# Hardwiring.net
KiCad netlist of a schematic drawn in Altium Designer
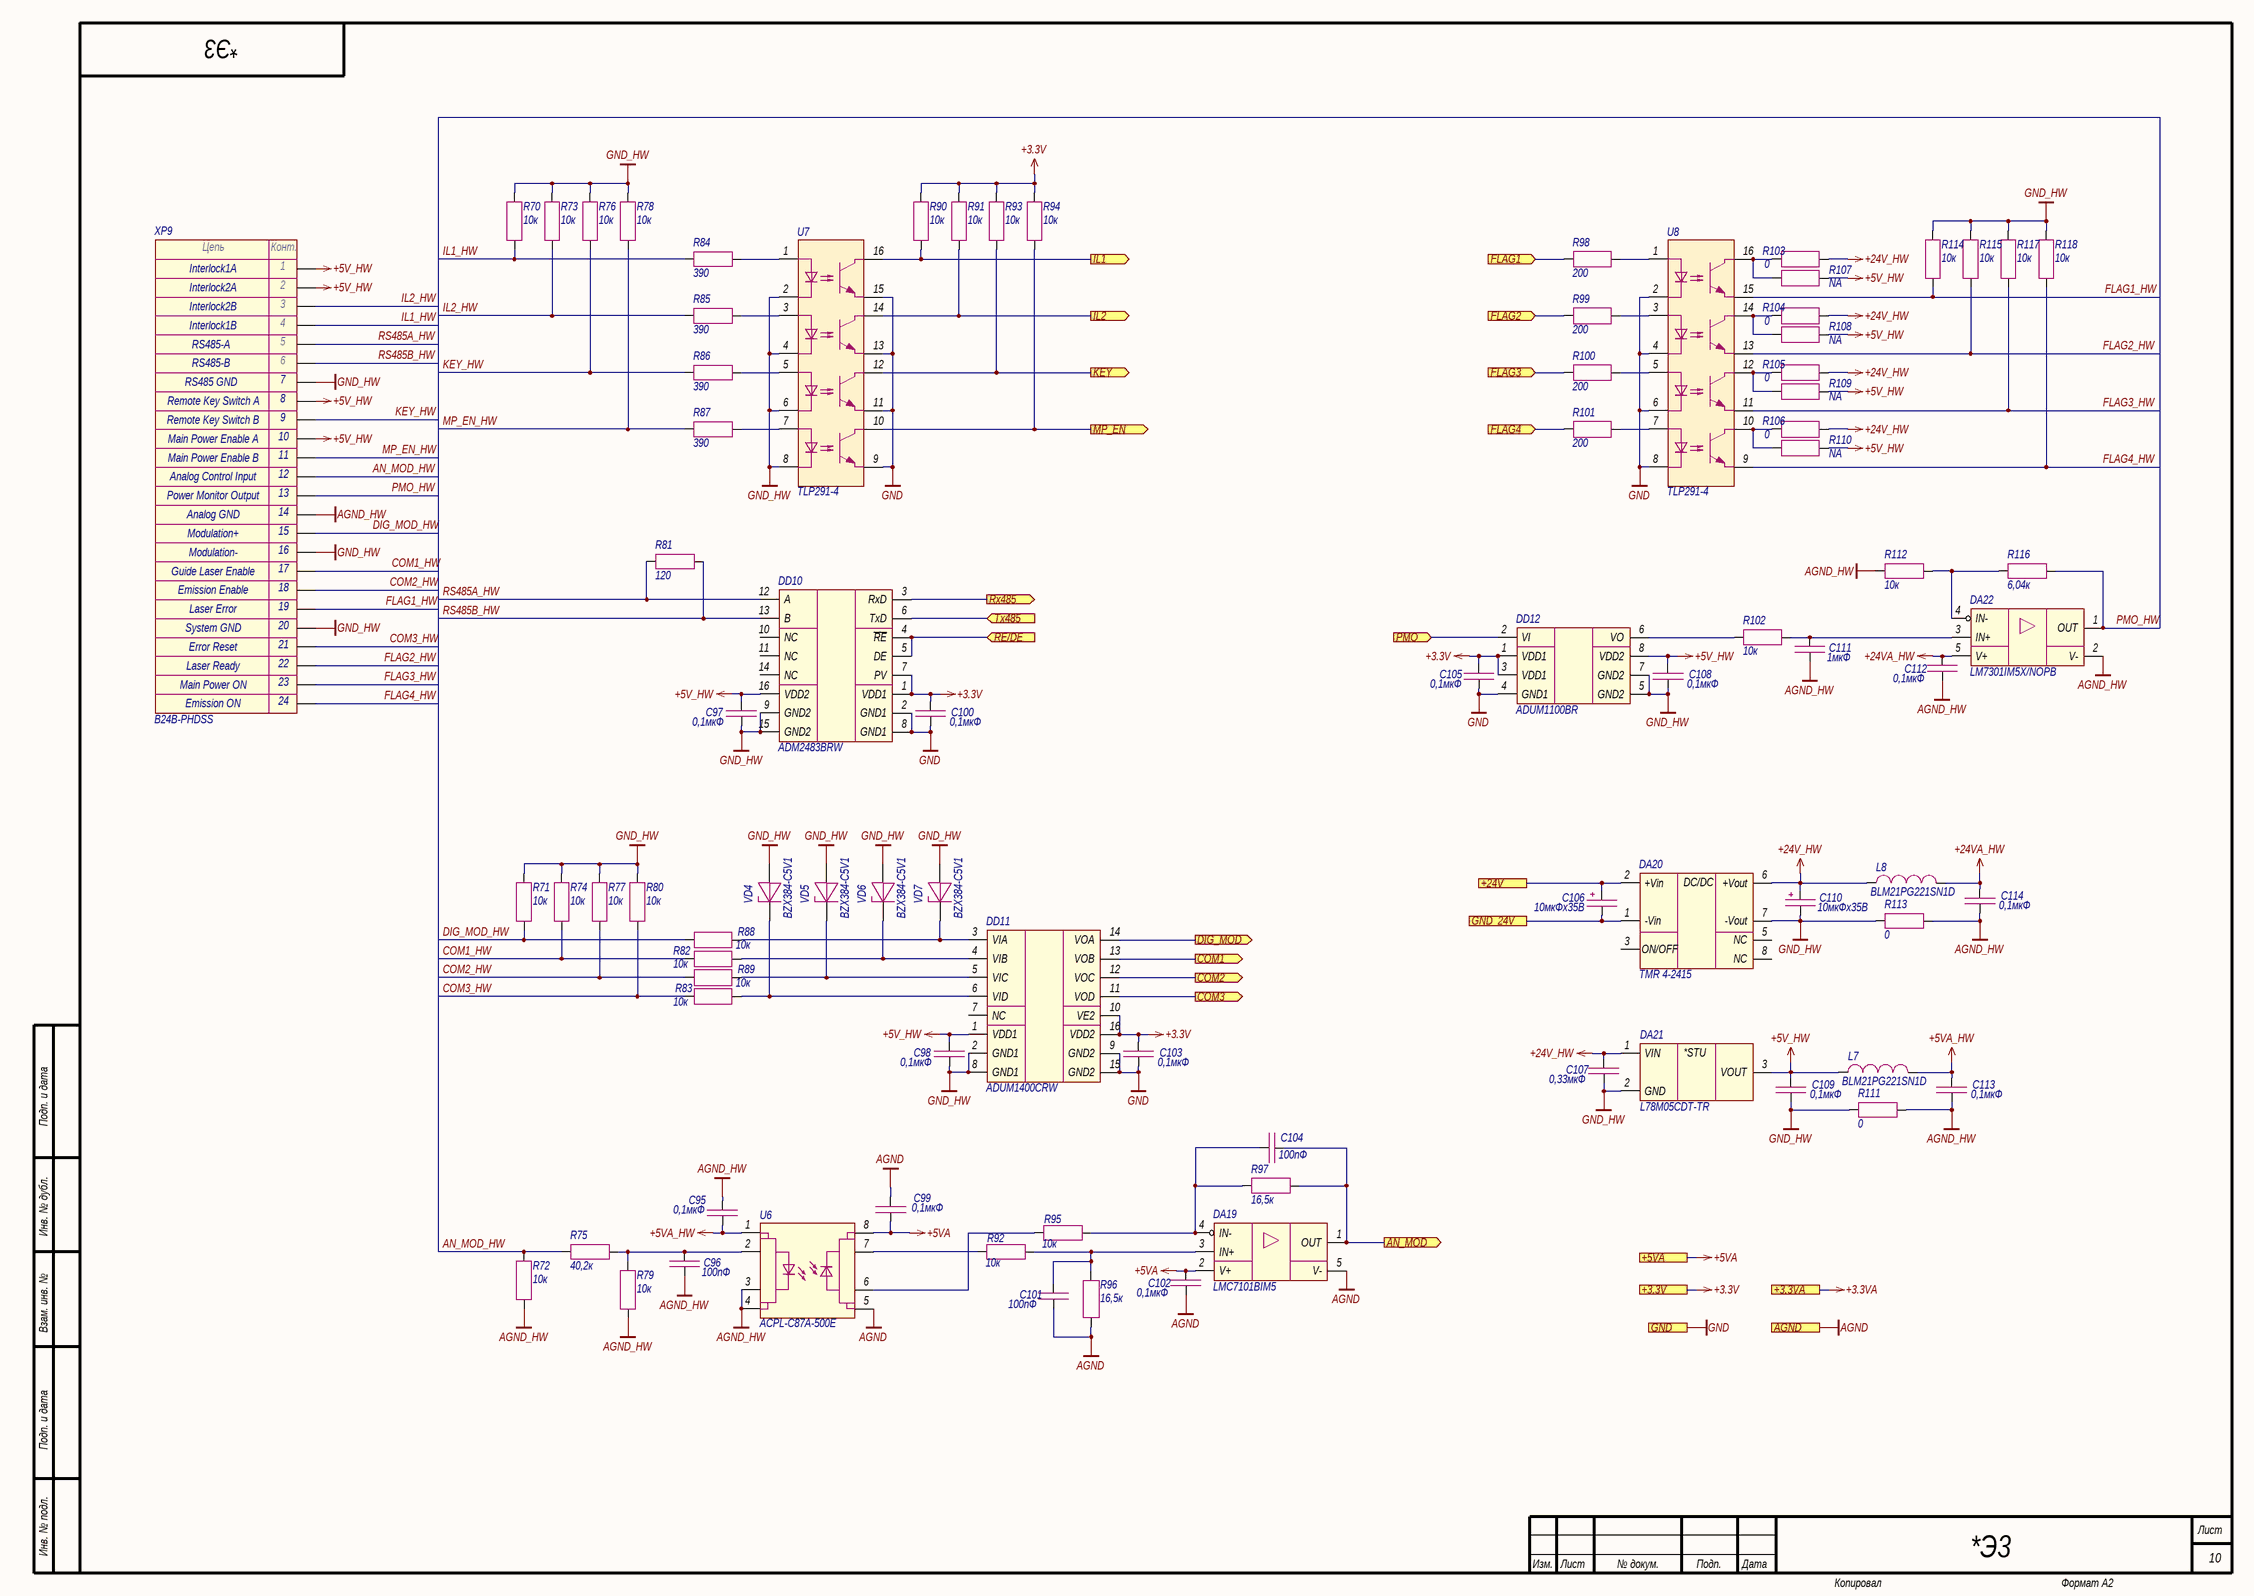
[diagram p0: Hardwiring.SchDoc]

(export (version "E")
  (design (tool "Eeschema 10.0.6"))
  (components
    (comp (ref "C95")
      (value "0,1мкФ")
      (footprint "Pcb_library:CAP_0603")
      (fields (field (name "MANUFACTURER") "Murata"))
      (libsource (lib "Schem_library") (part "Capacitor"))
    )
    (comp (ref "C96")
      (value "100пФ")
      (footprint "Pcb_library:CAP_0603")
      (fields (field (name "MANUFACTURER") "Murata"))
      (libsource (lib "Schem_library") (part "Capacitor"))
    )
    (comp (ref "C97")
      (value "0,1мкФ")
      (footprint "Pcb_library:CAP_0603")
      (fields (field (name "MANUFACTURER") "Murata"))
      (libsource (lib "Schem_library") (part "Capacitor"))
    )
    (comp (ref "C98")
      (value "0,1мкФ")
      (footprint "Pcb_library:CAP_0603")
      (fields (field (name "MANUFACTURER") "Murata"))
      (libsource (lib "Schem_library") (part "Capacitor"))
    )
    (comp (ref "C99")
      (value "0,1мкФ")
      (footprint "Pcb_library:CAP_0603")
      (fields (field (name "MANUFACTURER") "Murata"))
      (libsource (lib "Schem_library") (part "Capacitor"))
    )
    (comp (ref "C100")
      (value "0,1мкФ")
      (footprint "Pcb_library:CAP_0603")
      (fields (field (name "MANUFACTURER") "Murata"))
      (libsource (lib "Schem_library") (part "Capacitor"))
    )
    (comp (ref "C101")
      (value "100пФ")
      (footprint "Pcb_library:CAP_0603")
      (fields (field (name "MANUFACTURER") "Murata"))
      (libsource (lib "Schem_library") (part "Capacitor"))
    )
    (comp (ref "C102")
      (value "0,1мкФ")
      (footprint "Pcb_library:CAP_0603")
      (fields (field (name "MANUFACTURER") "Murata"))
      (libsource (lib "Schem_library") (part "Capacitor"))
    )
    (comp (ref "C103")
      (value "0,1мкФ")
      (footprint "Pcb_library:CAP_0603")
      (fields (field (name "MANUFACTURER") "Murata"))
      (libsource (lib "Schem_library") (part "Capacitor"))
    )
    (comp (ref "C104")
      (value "100пФ")
      (footprint "Pcb_library:CAP_0603")
      (fields (field (name "MANUFACTURER") "Murata"))
      (libsource (lib "Schem_library") (part "Capacitor"))
    )
    (comp (ref "C105")
      (value "0,1мкФ")
      (footprint "Pcb_library:CAP_0603")
      (fields (field (name "MANUFACTURER") "Murata"))
      (libsource (lib "Schem_library") (part "Capacitor"))
    )
    (comp (ref "C106")
      (value "10мкФх35B")
      (footprint "Pcb_library:CAP_C")
      (libsource (lib "Schem_library") (part "Capacitor_Polar"))
    )
    (comp (ref "C107")
      (value "0,33мкФ")
      (footprint "Pcb_library:CAP_0805")
      (fields (field (name "MANUFACTURER") "Murata"))
      (libsource (lib "Schem_library") (part "Capacitor"))
    )
    (comp (ref "C108")
      (value "0,1мкФ")
      (footprint "Pcb_library:CAP_0603")
      (fields (field (name "MANUFACTURER") "Murata"))
      (libsource (lib "Schem_library") (part "Capacitor"))
    )
    (comp (ref "C109")
      (value "0,1мкФ")
      (footprint "Pcb_library:CAP_0603")
      (fields (field (name "MANUFACTURER") "Murata"))
      (libsource (lib "Schem_library") (part "Capacitor"))
    )
    (comp (ref "C110")
      (value "10мкФх35B")
      (footprint "Pcb_library:CAP_C")
      (libsource (lib "") (part "Capacitor_Polar_1"))
    )
    (comp (ref "C111")
      (value "1мкФ")
      (footprint "Pcb_library:CAP_0603")
      (fields (field (name "MANUFACTURER") "Murata"))
      (libsource (lib "Schem_library") (part "Capacitor"))
    )
    (comp (ref "C112")
      (value "0,1мкФ")
      (footprint "Pcb_library:CAP_0603")
      (fields (field (name "MANUFACTURER") "Murata"))
      (libsource (lib "Schem_library") (part "Capacitor"))
    )
    (comp (ref "C113")
      (value "0,1мкФ")
      (footprint "Pcb_library:CAP_0603")
      (fields (field (name "MANUFACTURER") "Murata"))
      (libsource (lib "Schem_library") (part "Capacitor"))
    )
    (comp (ref "C114")
      (value "0,1мкФ")
      (footprint "Pcb_library:CAP_0603")
      (fields (field (name "MANUFACTURER") "Murata"))
      (libsource (lib "Schem_library") (part "Capacitor"))
    )
    (comp (ref "DA19")
      (value "LMC7101BIM5")
      (footprint "Pcb_library:SOT-23-5")
      (fields (field (name "MANUFACTURER") "Texas Instruments"))
      (libsource (lib "Schem_library") (part "LMC7101"))
    )
    (comp (ref "DA20")
      (value "TMR 4-2415")
      (footprint "Pcb_library:TMR4 (SIP-8)")
      (fields (field (name "MANUFACTURER") "Traco Power"))
      (libsource (lib "Schem_library") (part "TMR4"))
    )
    (comp (ref "DA21")
      (value "L78M05CDT-TR")
      (footprint "Pcb_library:TO-252")
      (fields (field (name "MANUFACTURER") "STMicroelectronics"))
      (libsource (lib "Schem_library") (part "L78M"))
    )
    (comp (ref "DA22")
      (value "LM7301IM5X/NOPB")
      (footprint "Pcb_library:SOT-23-5")
      (fields (field (name "MANUFACTURER") "Texas Instruments"))
      (libsource (lib "Schem_library") (part "LM7301IM5"))
    )
    (comp (ref "DD10")
      (value "ADM2483BRW")
      (footprint "Pcb_library:SOIC-16W")
      (fields (field (name "MANUFACTURER") "Analog Devices"))
      (libsource (lib "Schem_library") (part "ADM2483BRW"))
    )
    (comp (ref "DD11")
      (value "ADUM1400CRW")
      (footprint "Pcb_library:SOIC-16W")
      (fields (field (name "MANUFACTURER") "Analog Devices"))
      (libsource (lib "Schem_library") (part "ADUM1400"))
    )
    (comp (ref "DD12")
      (value "ADUM1100BR")
      (footprint "Pcb_library:SOIC-8")
      (fields (field (name "MANUFACTURER") "Analog Devices"))
      (libsource (lib "Schem_library") (part "ADUM1100"))
    )
    (comp (ref "L7")
      (value "BLM21PG221SN1D")
      (footprint "Pcb_library:IND_0805")
      (fields (field (name "MANUFACTURER") "Murata"))
      (libsource (lib "Schem_library") (part "Inductor"))
    )
    (comp (ref "L8")
      (value "BLM21PG221SN1D")
      (footprint "Pcb_library:IND_0805")
      (fields (field (name "MANUFACTURER") "Murata"))
      (libsource (lib "Schem_library") (part "Inductor"))
    )
    (comp (ref "R70")
      (value "10к")
      (footprint "Pcb_library:RES_0603")
      (fields (field (name "MANUFACTURER") "Yageo"))
      (libsource (lib "Schem_library") (part "Resistor"))
    )
    (comp (ref "R71")
      (value "10к")
      (footprint "Pcb_library:RES_0603")
      (fields (field (name "MANUFACTURER") "Yageo"))
      (libsource (lib "Schem_library") (part "Resistor"))
    )
    (comp (ref "R72")
      (value "10к")
      (footprint "Pcb_library:RES_0603")
      (fields (field (name "MANUFACTURER") "Yageo"))
      (libsource (lib "Schem_library") (part "Resistor"))
    )
    (comp (ref "R73")
      (value "10к")
      (footprint "Pcb_library:RES_0603")
      (fields (field (name "MANUFACTURER") "Yageo"))
      (libsource (lib "Schem_library") (part "Resistor"))
    )
    (comp (ref "R74")
      (value "10к")
      (footprint "Pcb_library:RES_0603")
      (fields (field (name "MANUFACTURER") "Yageo"))
      (libsource (lib "Schem_library") (part "Resistor"))
    )
    (comp (ref "R75")
      (value "40,2к")
      (footprint "Pcb_library:RES_0603")
      (fields (field (name "MANUFACTURER") "Yageo"))
      (libsource (lib "Schem_library") (part "Resistor"))
    )
    (comp (ref "R76")
      (value "10к")
      (footprint "Pcb_library:RES_0603")
      (fields (field (name "MANUFACTURER") "Yageo"))
      (libsource (lib "Schem_library") (part "Resistor"))
    )
    (comp (ref "R77")
      (value "10к")
      (footprint "Pcb_library:RES_0603")
      (fields (field (name "MANUFACTURER") "Yageo"))
      (libsource (lib "Schem_library") (part "Resistor"))
    )
    (comp (ref "R78")
      (value "10к")
      (footprint "Pcb_library:RES_0603")
      (fields (field (name "MANUFACTURER") "Yageo"))
      (libsource (lib "Schem_library") (part "Resistor"))
    )
    (comp (ref "R79")
      (value "10к")
      (footprint "Pcb_library:RES_0603")
      (fields (field (name "MANUFACTURER") "Yageo"))
      (libsource (lib "Schem_library") (part "Resistor"))
    )
    (comp (ref "R80")
      (value "10к")
      (footprint "Pcb_library:RES_0603")
      (fields (field (name "MANUFACTURER") "Yageo"))
      (libsource (lib "Schem_library") (part "Resistor"))
    )
    (comp (ref "R81")
      (value "120")
      (footprint "Pcb_library:RES_0805")
      (fields (field (name "MANUFACTURER") "Yageo"))
      (libsource (lib "Schem_library") (part "Resistor"))
    )
    (comp (ref "R82")
      (value "10к")
      (footprint "Pcb_library:RES_0603")
      (fields (field (name "MANUFACTURER") "Yageo"))
      (libsource (lib "Schem_library") (part "Resistor"))
    )
    (comp (ref "R83")
      (value "10к")
      (footprint "Pcb_library:RES_0603")
      (fields (field (name "MANUFACTURER") "Yageo"))
      (libsource (lib "Schem_library") (part "Resistor"))
    )
    (comp (ref "R84")
      (value "390")
      (footprint "Pcb_library:RES_0603")
      (fields (field (name "MANUFACTURER") "Yageo"))
      (libsource (lib "Schem_library") (part "Resistor"))
    )
    (comp (ref "R85")
      (value "390")
      (footprint "Pcb_library:RES_0603")
      (fields (field (name "MANUFACTURER") "Yageo"))
      (libsource (lib "Schem_library") (part "Resistor"))
    )
    (comp (ref "R86")
      (value "390")
      (footprint "Pcb_library:RES_0603")
      (fields (field (name "MANUFACTURER") "Yageo"))
      (libsource (lib "Schem_library") (part "Resistor"))
    )
    (comp (ref "R87")
      (value "390")
      (footprint "Pcb_library:RES_0603")
      (fields (field (name "MANUFACTURER") "Yageo"))
      (libsource (lib "Schem_library") (part "Resistor"))
    )
    (comp (ref "R88")
      (value "10к")
      (footprint "Pcb_library:RES_0603")
      (fields (field (name "MANUFACTURER") "Yageo"))
      (libsource (lib "Schem_library") (part "Resistor"))
    )
    (comp (ref "R89")
      (value "10к")
      (footprint "Pcb_library:RES_0603")
      (fields (field (name "MANUFACTURER") "Yageo"))
      (libsource (lib "Schem_library") (part "Resistor"))
    )
    (comp (ref "R90")
      (value "10к")
      (footprint "Pcb_library:RES_0603")
      (fields (field (name "MANUFACTURER") "Yageo"))
      (libsource (lib "Schem_library") (part "Resistor"))
    )
    (comp (ref "R91")
      (value "10к")
      (footprint "Pcb_library:RES_0603")
      (fields (field (name "MANUFACTURER") "Yageo"))
      (libsource (lib "Schem_library") (part "Resistor"))
    )
    (comp (ref "R92")
      (value "10к")
      (footprint "Pcb_library:RES_0603")
      (fields (field (name "MANUFACTURER") "Yageo"))
      (libsource (lib "Schem_library") (part "Resistor"))
    )
    (comp (ref "R93")
      (value "10к")
      (footprint "Pcb_library:RES_0603")
      (fields (field (name "MANUFACTURER") "Yageo"))
      (libsource (lib "Schem_library") (part "Resistor"))
    )
    (comp (ref "R94")
      (value "10к")
      (footprint "Pcb_library:RES_0603")
      (fields (field (name "MANUFACTURER") "Yageo"))
      (libsource (lib "Schem_library") (part "Resistor"))
    )
    (comp (ref "R95")
      (value "10к")
      (footprint "Pcb_library:RES_0603")
      (fields (field (name "MANUFACTURER") "Yageo"))
      (libsource (lib "Schem_library") (part "Resistor"))
    )
    (comp (ref "R96")
      (value "16,5к")
      (footprint "Pcb_library:RES_0603")
      (fields (field (name "MANUFACTURER") "Yageo"))
      (libsource (lib "Schem_library") (part "Resistor"))
    )
    (comp (ref "R97")
      (value "16,5к")
      (footprint "Pcb_library:RES_0603")
      (fields (field (name "MANUFACTURER") "Yageo"))
      (libsource (lib "Schem_library") (part "Resistor"))
    )
    (comp (ref "R98")
      (value "200")
      (footprint "Pcb_library:RES_0603")
      (fields (field (name "MANUFACTURER") "Yageo"))
      (libsource (lib "Schem_library") (part "Resistor"))
    )
    (comp (ref "R99")
      (value "200")
      (footprint "Pcb_library:RES_0603")
      (fields (field (name "MANUFACTURER") "Yageo"))
      (libsource (lib "Schem_library") (part "Resistor"))
    )
    (comp (ref "R100")
      (value "200")
      (footprint "Pcb_library:RES_0603")
      (fields (field (name "MANUFACTURER") "Yageo"))
      (libsource (lib "Schem_library") (part "Resistor"))
    )
    (comp (ref "R101")
      (value "200")
      (footprint "Pcb_library:RES_0603")
      (fields (field (name "MANUFACTURER") "Yageo"))
      (libsource (lib "Schem_library") (part "Resistor"))
    )
    (comp (ref "R102")
      (value "10к")
      (footprint "Pcb_library:RES_0603")
      (fields (field (name "MANUFACTURER") "Yageo"))
      (libsource (lib "Schem_library") (part "Resistor"))
    )
    (comp (ref "R103")
      (value "0")
      (footprint "Pcb_library:RES_0603")
      (fields (field (name "MANUFACTURER") "Yageo"))
      (libsource (lib "Schem_library") (part "Resistor"))
    )
    (comp (ref "R104")
      (value "0")
      (footprint "Pcb_library:RES_0603")
      (fields (field (name "MANUFACTURER") "Yageo"))
      (libsource (lib "Schem_library") (part "Resistor"))
    )
    (comp (ref "R105")
      (value "0")
      (footprint "Pcb_library:RES_0603")
      (fields (field (name "MANUFACTURER") "Yageo"))
      (libsource (lib "Schem_library") (part "Resistor"))
    )
    (comp (ref "R106")
      (value "0")
      (footprint "Pcb_library:RES_0603")
      (fields (field (name "MANUFACTURER") "Yageo"))
      (libsource (lib "Schem_library") (part "Resistor"))
    )
    (comp (ref "R107")
      (value "NA")
      (footprint "Pcb_library:RES_0603")
      (libsource (lib "Schem_library") (part "Resistor"))
    )
    (comp (ref "R108")
      (value "NA")
      (footprint "Pcb_library:RES_0603")
      (libsource (lib "Schem_library") (part "Resistor"))
    )
    (comp (ref "R109")
      (value "NA")
      (footprint "Pcb_library:RES_0603")
      (libsource (lib "Schem_library") (part "Resistor"))
    )
    (comp (ref "R110")
      (value "NA")
      (footprint "Pcb_library:RES_0603")
      (libsource (lib "Schem_library") (part "Resistor"))
    )
    (comp (ref "R111")
      (value "0")
      (footprint "Pcb_library:RES_0805")
      (fields (field (name "MANUFACTURER") "Yageo"))
      (libsource (lib "Schem_library") (part "Resistor"))
    )
    (comp (ref "R112")
      (value "10к")
      (footprint "Pcb_library:RES_0603")
      (fields (field (name "MANUFACTURER") "Yageo"))
      (libsource (lib "Schem_library") (part "Resistor"))
    )
    (comp (ref "R113")
      (value "0")
      (footprint "Pcb_library:RES_0805")
      (fields (field (name "MANUFACTURER") "Yageo"))
      (libsource (lib "Schem_library") (part "Resistor"))
    )
    (comp (ref "R114")
      (value "10к")
      (footprint "Pcb_library:RES_0603")
      (fields (field (name "MANUFACTURER") "Yageo"))
      (libsource (lib "Schem_library") (part "Resistor"))
    )
    (comp (ref "R115")
      (value "10к")
      (footprint "Pcb_library:RES_0603")
      (fields (field (name "MANUFACTURER") "Yageo"))
      (libsource (lib "Schem_library") (part "Resistor"))
    )
    (comp (ref "R116")
      (value "6,04к")
      (footprint "Pcb_library:RES_0603")
      (fields (field (name "MANUFACTURER") "Yageo"))
      (libsource (lib "Schem_library") (part "Resistor"))
    )
    (comp (ref "R117")
      (value "10к")
      (footprint "Pcb_library:RES_0603")
      (fields (field (name "MANUFACTURER") "Yageo"))
      (libsource (lib "Schem_library") (part "Resistor"))
    )
    (comp (ref "R118")
      (value "10к")
      (footprint "Pcb_library:RES_0603")
      (fields (field (name "MANUFACTURER") "Yageo"))
      (libsource (lib "Schem_library") (part "Resistor"))
    )
    (comp (ref "U6")
      (value "ACPL-C87A-500E")
      (footprint "Pcb_library:SSO-8")
      (fields (field (name "MANUFACTURER") "Broadcom"))
      (libsource (lib "Schem_library") (part "ACPL-C87"))
    )
    (comp (ref "U7")
      (value "TLP291-4")
      (footprint "Pcb_library:SOP-16")
      (fields (field (name "MANUFACTURER") "Toshiba"))
      (libsource (lib "Schem_library") (part "TLP281-4"))
    )
    (comp (ref "U8")
      (value "TLP291-4")
      (footprint "Pcb_library:SOP-16")
      (fields (field (name "MANUFACTURER") "Toshiba"))
      (libsource (lib "Schem_library") (part "TLP281-4"))
    )
    (comp (ref "VD4")
      (value "BZX384-C5V1")
      (footprint "Pcb_library:SOD-323")
      (fields (field (name "MANUFACTURER") "Nexperia"))
      (libsource (lib "Schem_library") (part "Diode_Zener"))
    )
    (comp (ref "VD5")
      (value "BZX384-C5V1")
      (footprint "Pcb_library:SOD-323")
      (fields (field (name "MANUFACTURER") "Nexperia"))
      (libsource (lib "Schem_library") (part "Diode_Zener"))
    )
    (comp (ref "VD6")
      (value "BZX384-C5V1")
      (footprint "Pcb_library:SOD-323")
      (fields (field (name "MANUFACTURER") "Nexperia"))
      (libsource (lib "Schem_library") (part "Diode_Zener"))
    )
    (comp (ref "VD7")
      (value "BZX384-C5V1")
      (footprint "Pcb_library:SOD-323")
      (fields (field (name "MANUFACTURER") "Nexperia"))
      (libsource (lib "Schem_library") (part "Diode_Zener"))
    )
    (comp (ref "XP9")
      (value "B24B-PHDSS")
      (footprint "Pcb_library:B24B-PHDSS")
      (fields (field (name "MANUFACTURER") "JST"))
      (libsource (lib "Schem_library") (part "Connector-24"))
    )
  )
  (nets
    (net (code "1") (name "+3.3V") (class "Default")
      (node (ref "C100") (pin "1") (pinfunction "1_1") (pintype "passive"))
      (node (ref "C103") (pin "1") (pinfunction "1_1") (pintype "passive"))
      (node (ref "C105") (pin "1") (pinfunction "1_1") (pintype "passive"))
      (node (ref "DD10") (pin "1") (pinfunction "VDD1_1") (pintype "passive"))
      (node (ref "DD10") (pin "7") (pinfunction "PV_7") (pintype "passive"))
      (node (ref "DD11") (pin "10") (pinfunction "VE2_10") (pintype "passive"))
      (node (ref "DD11") (pin "16") (pinfunction "VDD2_16") (pintype "passive"))
      (node (ref "DD12") (pin "1") (pinfunction "VDD1_1") (pintype "passive"))
      (node (ref "DD12") (pin "3") (pinfunction "VDD1_3") (pintype "passive"))
      (node (ref "R90") (pin "1") (pinfunction "1_1") (pintype "passive"))
      (node (ref "R91") (pin "1") (pinfunction "1_1") (pintype "passive"))
      (node (ref "R93") (pin "1") (pinfunction "1_1") (pintype "passive"))
      (node (ref "R94") (pin "1") (pinfunction "1_1") (pintype "passive"))
    )
    (net (code "3") (name "+5VA") (class "Default")
      (node (ref "C102") (pin "1") (pinfunction "1_1") (pintype "passive"))
      (node (ref "C99") (pin "1") (pinfunction "1_1") (pintype "passive"))
      (node (ref "DA19") (pin "2") (pinfunction "V+_2") (pintype "passive"))
      (node (ref "U6") (pin "8") (pinfunction "VDD2_8") (pintype "passive"))
    )
    (net (code "4") (name "+5VA_HW") (class "Default")
      (node (ref "C113") (pin "1") (pinfunction "1_1") (pintype "passive"))
      (node (ref "C95") (pin "1") (pinfunction "1_1") (pintype "passive"))
      (node (ref "L7") (pin "2") (pinfunction "2_2") (pintype "passive"))
      (node (ref "U6") (pin "1") (pinfunction "VDD1_1") (pintype "passive"))
    )
    (net (code "5") (name "+5V_HW") (class "Default")
      (node (ref "C108") (pin "1") (pinfunction "1_1") (pintype "passive"))
      (node (ref "C109") (pin "1") (pinfunction "1_1") (pintype "passive"))
      (node (ref "C97") (pin "1") (pinfunction "1_1") (pintype "passive"))
      (node (ref "C98") (pin "1") (pinfunction "1_1") (pintype "passive"))
      (node (ref "DA21") (pin "3") (pinfunction "VOUT_3") (pintype "passive"))
      (node (ref "DD10") (pin "16") (pinfunction "VDD2_16") (pintype "passive"))
      (node (ref "DD11") (pin "1") (pinfunction "VDD1_1") (pintype "passive"))
      (node (ref "DD12") (pin "8") (pinfunction "VDD2_8") (pintype "passive"))
      (node (ref "L7") (pin "1") (pinfunction "1_1") (pintype "passive"))
      (node (ref "R107") (pin "2") (pinfunction "2_2") (pintype "passive"))
      (node (ref "R108") (pin "2") (pinfunction "2_2") (pintype "passive"))
      (node (ref "R109") (pin "2") (pinfunction "2_2") (pintype "passive"))
      (node (ref "R110") (pin "2") (pinfunction "2_2") (pintype "passive"))
      (node (ref "XP9") (pin "1") (pintype "passive"))
      (node (ref "XP9") (pin "10") (pintype "passive"))
      (node (ref "XP9") (pin "2") (pintype "passive"))
      (node (ref "XP9") (pin "8") (pintype "passive"))
    )
    (net (code "6") (name "+24VA_HW") (class "Default")
      (node (ref "C112") (pin "1") (pinfunction "1_1") (pintype "passive"))
      (node (ref "C114") (pin "1") (pinfunction "1_1") (pintype "passive"))
      (node (ref "DA22") (pin "5") (pinfunction "V+_5") (pintype "passive"))
      (node (ref "L8") (pin "2") (pinfunction "2_2") (pintype "passive"))
    )
    (net (code "7") (name "+24V_HW") (class "Default")
      (node (ref "C107") (pin "2") (pinfunction "2_2") (pintype "passive"))
      (node (ref "C110") (pin "1") (pinfunction "1_1") (pintype "passive"))
      (node (ref "DA20") (pin "6") (pinfunction "+Vout_6") (pintype "passive"))
      (node (ref "DA21") (pin "1") (pinfunction "VIN_1") (pintype "passive"))
      (node (ref "L8") (pin "1") (pinfunction "1_1") (pintype "passive"))
      (node (ref "R103") (pin "2") (pinfunction "2_2") (pintype "passive"))
      (node (ref "R104") (pin "2") (pinfunction "2_2") (pintype "passive"))
      (node (ref "R105") (pin "2") (pinfunction "2_2") (pintype "passive"))
      (node (ref "R106") (pin "2") (pinfunction "2_2") (pintype "passive"))
    )
    (net (code "8") (name "/+24V") (class "Default")
      (node (ref "C106") (pin "1") (pinfunction "1_1") (pintype "passive"))
      (node (ref "DA20") (pin "2") (pinfunction "+Vin_2") (pintype "passive"))
    )
    (net (code "9") (name "/AN_MOD") (class "Default")
      (node (ref "C104") (pin "2") (pinfunction "2_2") (pintype "passive"))
      (node (ref "DA19") (pin "1") (pinfunction "OUT_1") (pintype "passive"))
      (node (ref "R97") (pin "1") (pinfunction "1_1") (pintype "passive"))
    )
    (net (code "10") (name "/AN_MOD_HW") (class "Default")
      (node (ref "R72") (pin "1") (pinfunction "1_1") (pintype "passive"))
      (node (ref "R75") (pin "2") (pinfunction "2_2") (pintype "passive"))
      (node (ref "XP9") (pin "12") (pintype "passive"))
    )
    (net (code "11") (name "/COM1") (class "Default")
      (node (ref "DD11") (pin "13") (pinfunction "VOB_13") (pintype "passive"))
    )
    (net (code "12") (name "/COM1_HW") (class "Default")
      (node (ref "R74") (pin "2") (pinfunction "2_2") (pintype "passive"))
      (node (ref "R82") (pin "1") (pinfunction "1_1") (pintype "passive"))
      (node (ref "XP9") (pin "17") (pintype "passive"))
    )
    (net (code "13") (name "/COM2") (class "Default")
      (node (ref "DD11") (pin "12") (pinfunction "VOC_12") (pintype "passive"))
    )
    (net (code "14") (name "/COM2_HW") (class "Default")
      (node (ref "R77") (pin "2") (pinfunction "2_2") (pintype "passive"))
      (node (ref "R89") (pin "1") (pinfunction "1_1") (pintype "passive"))
      (node (ref "XP9") (pin "18") (pintype "passive"))
    )
    (net (code "15") (name "/COM3") (class "Default")
      (node (ref "DD11") (pin "11") (pinfunction "VOD_11") (pintype "passive"))
    )
    (net (code "16") (name "/COM3_HW") (class "Default")
      (node (ref "R80") (pin "2") (pinfunction "2_2") (pintype "passive"))
      (node (ref "R83") (pin "1") (pinfunction "1_1") (pintype "passive"))
      (node (ref "XP9") (pin "21") (pintype "passive"))
    )
    (net (code "17") (name "/DIG_MOD") (class "Default")
      (node (ref "DD11") (pin "14") (pinfunction "VOA_14") (pintype "passive"))
    )
    (net (code "18") (name "/DIG_MOD_HW") (class "Default")
      (node (ref "R71") (pin "2") (pinfunction "2_2") (pintype "passive"))
      (node (ref "R88") (pin "1") (pinfunction "1_1") (pintype "passive"))
      (node (ref "XP9") (pin "15") (pintype "passive"))
    )
    (net (code "19") (name "/FLAG1") (class "Default")
      (node (ref "R98") (pin "2") (pinfunction "2_2") (pintype "passive"))
    )
    (net (code "20") (name "/FLAG1_HW") (class "Default")
      (node (ref "R114") (pin "2") (pinfunction "2_2") (pintype "passive"))
      (node (ref "U8") (pin "15") (pintype "passive"))
      (node (ref "XP9") (pin "19") (pintype "passive"))
    )
    (net (code "21") (name "/FLAG2") (class "Default")
      (node (ref "R99") (pin "2") (pinfunction "2_2") (pintype "passive"))
    )
    (net (code "22") (name "/FLAG2_HW") (class "Default")
      (node (ref "R115") (pin "2") (pinfunction "2_2") (pintype "passive"))
      (node (ref "U8") (pin "13") (pintype "passive"))
      (node (ref "XP9") (pin "22") (pintype "passive"))
    )
    (net (code "23") (name "/FLAG3") (class "Default")
      (node (ref "R100") (pin "2") (pinfunction "2_2") (pintype "passive"))
    )
    (net (code "24") (name "/FLAG3_HW") (class "Default")
      (node (ref "R117") (pin "2") (pinfunction "2_2") (pintype "passive"))
      (node (ref "U8") (pin "11") (pintype "passive"))
      (node (ref "XP9") (pin "23") (pintype "passive"))
    )
    (net (code "25") (name "/FLAG4") (class "Default")
      (node (ref "R101") (pin "2") (pinfunction "2_2") (pintype "passive"))
    )
    (net (code "26") (name "/FLAG4_HW") (class "Default")
      (node (ref "R118") (pin "2") (pinfunction "2_2") (pintype "passive"))
      (node (ref "U8") (pin "9") (pintype "passive"))
      (node (ref "XP9") (pin "24") (pintype "passive"))
    )
    (net (code "27") (name "/GND_24V") (class "Default")
      (node (ref "C106") (pin "2") (pinfunction "2_2") (pintype "passive"))
      (node (ref "DA20") (pin "1") (pinfunction "-Vin_1") (pintype "passive"))
    )
    (net (code "28") (name "/IL1") (class "Default")
      (node (ref "R90") (pin "2") (pinfunction "2_2") (pintype "passive"))
      (node (ref "U7") (pin "16") (pintype "passive"))
    )
    (net (code "29") (name "/IL1_HW") (class "Default")
      (node (ref "R70") (pin "2") (pinfunction "2_2") (pintype "passive"))
      (node (ref "R84") (pin "1") (pinfunction "1_1") (pintype "passive"))
      (node (ref "XP9") (pin "4") (pintype "passive"))
    )
    (net (code "30") (name "/IL2") (class "Default")
      (node (ref "R91") (pin "2") (pinfunction "2_2") (pintype "passive"))
      (node (ref "U7") (pin "14") (pintype "passive"))
    )
    (net (code "31") (name "/IL2_HW") (class "Default")
      (node (ref "R73") (pin "2") (pinfunction "2_2") (pintype "passive"))
      (node (ref "R85") (pin "1") (pinfunction "1_1") (pintype "passive"))
      (node (ref "XP9") (pin "3") (pintype "passive"))
    )
    (net (code "32") (name "/KEY") (class "Default")
      (node (ref "R93") (pin "2") (pinfunction "2_2") (pintype "passive"))
      (node (ref "U7") (pin "12") (pintype "passive"))
    )
    (net (code "33") (name "/KEY_HW") (class "Default")
      (node (ref "R76") (pin "2") (pinfunction "2_2") (pintype "passive"))
      (node (ref "R86") (pin "1") (pinfunction "1_1") (pintype "passive"))
      (node (ref "XP9") (pin "9") (pintype "passive"))
    )
    (net (code "34") (name "/MP_EN") (class "Default")
      (node (ref "R94") (pin "2") (pinfunction "2_2") (pintype "passive"))
      (node (ref "U7") (pin "10") (pintype "passive"))
    )
    (net (code "35") (name "/MP_EN_HW") (class "Default")
      (node (ref "R78") (pin "2") (pinfunction "2_2") (pintype "passive"))
      (node (ref "R87") (pin "1") (pinfunction "1_1") (pintype "passive"))
      (node (ref "XP9") (pin "11") (pintype "passive"))
    )
    (net (code "36") (name "/PMO") (class "Default")
      (node (ref "DD12") (pin "2") (pinfunction "VI_2") (pintype "passive"))
    )
    (net (code "37") (name "/PMO_HW") (class "Default")
      (node (ref "DA22") (pin "1") (pinfunction "OUT_1") (pintype "passive"))
      (node (ref "R116") (pin "2") (pinfunction "2_2") (pintype "passive"))
      (node (ref "XP9") (pin "13") (pintype "passive"))
    )
    (net (code "38") (name "/RE{slash}DE") (class "Default")
      (node (ref "DD10") (pin "4") (pinfunction "~{RE}_4") (pintype "passive"))
      (node (ref "DD10") (pin "5") (pinfunction "DE_5") (pintype "passive"))
    )
    (net (code "39") (name "/RS485A_HW") (class "Default")
      (node (ref "DD10") (pin "12") (pinfunction "A_12") (pintype "passive"))
      (node (ref "R81") (pin "1") (pinfunction "1_1") (pintype "passive"))
      (node (ref "XP9") (pin "5") (pintype "passive"))
    )
    (net (code "40") (name "/RS485B_HW") (class "Default")
      (node (ref "DD10") (pin "13") (pinfunction "B_13") (pintype "passive"))
      (node (ref "R81") (pin "2") (pinfunction "2_2") (pintype "passive"))
      (node (ref "XP9") (pin "6") (pintype "passive"))
    )
    (net (code "41") (name "/Rx485") (class "Default")
      (node (ref "DD10") (pin "3") (pinfunction "RxD_3") (pintype "passive"))
    )
    (net (code "42") (name "/Tx485") (class "Default")
      (node (ref "DD10") (pin "6") (pinfunction "TxD_6") (pintype "passive"))
    )
    (net (code "43") (name "AGND") (class "Default")
      (node (ref "C101") (pin "2") (pinfunction "2_2") (pintype "passive"))
      (node (ref "C102") (pin "2") (pinfunction "2_2") (pintype "passive"))
      (node (ref "C99") (pin "2") (pinfunction "2_2") (pintype "passive"))
      (node (ref "DA19") (pin "5") (pinfunction "V-_5") (pintype "passive"))
      (node (ref "R96") (pin "2") (pinfunction "2_2") (pintype "passive"))
      (node (ref "U6") (pin "5") (pinfunction "GND2_5") (pintype "passive"))
    )
    (net (code "44") (name "AGND_HW") (class "Default")
      (node (ref "C111") (pin "2") (pinfunction "2_2") (pintype "passive"))
      (node (ref "C112") (pin "2") (pinfunction "2_2") (pintype "passive"))
      (node (ref "C113") (pin "2") (pinfunction "2_2") (pintype "passive"))
      (node (ref "C114") (pin "2") (pinfunction "2_2") (pintype "passive"))
      (node (ref "C95") (pin "2") (pinfunction "2_2") (pintype "passive"))
      (node (ref "C96") (pin "1") (pinfunction "1_1") (pintype "passive"))
      (node (ref "DA22") (pin "2") (pinfunction "V-_2") (pintype "passive"))
      (node (ref "R111") (pin "2") (pinfunction "2_2") (pintype "passive"))
      (node (ref "R112") (pin "1") (pinfunction "1_1") (pintype "passive"))
      (node (ref "R113") (pin "2") (pinfunction "2_2") (pintype "passive"))
      (node (ref "R72") (pin "2") (pinfunction "2_2") (pintype "passive"))
      (node (ref "R79") (pin "2") (pinfunction "2_2") (pintype "passive"))
      (node (ref "U6") (pin "3") (pinfunction "SHDN_3") (pintype "passive"))
      (node (ref "U6") (pin "4") (pinfunction "GND1_4") (pintype "passive"))
      (node (ref "XP9") (pin "14") (pintype "passive"))
    )
    (net (code "45") (name "GND") (class "Default")
      (node (ref "C100") (pin "2") (pinfunction "2_2") (pintype "passive"))
      (node (ref "C103") (pin "2") (pinfunction "2_2") (pintype "passive"))
      (node (ref "C105") (pin "2") (pinfunction "2_2") (pintype "passive"))
      (node (ref "DD10") (pin "2") (pinfunction "GND1_2") (pintype "passive"))
      (node (ref "DD10") (pin "8") (pinfunction "GND1_8") (pintype "passive"))
      (node (ref "DD11") (pin "15") (pinfunction "GND2_15") (pintype "passive"))
      (node (ref "DD11") (pin "9") (pinfunction "GND2_9") (pintype "passive"))
      (node (ref "DD12") (pin "4") (pinfunction "GND1_4") (pintype "passive"))
      (node (ref "U7") (pin "11") (pintype "passive"))
      (node (ref "U7") (pin "13") (pintype "passive"))
      (node (ref "U7") (pin "15") (pintype "passive"))
      (node (ref "U7") (pin "9") (pintype "passive"))
      (node (ref "U8") (pin "2") (pintype "passive"))
      (node (ref "U8") (pin "4") (pintype "passive"))
      (node (ref "U8") (pin "6") (pintype "passive"))
      (node (ref "U8") (pin "8") (pintype "passive"))
    )
    (net (code "46") (name "GND_HW") (class "Default")
      (node (ref "C107") (pin "1") (pinfunction "1_1") (pintype "passive"))
      (node (ref "C108") (pin "2") (pinfunction "2_2") (pintype "passive"))
      (node (ref "C109") (pin "2") (pinfunction "2_2") (pintype "passive"))
      (node (ref "C110") (pin "2") (pinfunction "2_2") (pintype "passive"))
      (node (ref "C97") (pin "2") (pinfunction "2_2") (pintype "passive"))
      (node (ref "C98") (pin "2") (pinfunction "2_2") (pintype "passive"))
      (node (ref "DA20") (pin "7") (pinfunction "-Vout_7") (pintype "passive"))
      (node (ref "DA21") (pin "2") (pinfunction "GND_2") (pintype "passive"))
      (node (ref "DD10") (pin "15") (pinfunction "GND2_15") (pintype "passive"))
      (node (ref "DD10") (pin "9") (pinfunction "GND2_9") (pintype "passive"))
      (node (ref "DD11") (pin "2") (pinfunction "GND1_2") (pintype "passive"))
      (node (ref "DD11") (pin "8") (pinfunction "GND1_8") (pintype "passive"))
      (node (ref "DD12") (pin "5") (pinfunction "GND2_5") (pintype "passive"))
      (node (ref "DD12") (pin "7") (pinfunction "GND2_7") (pintype "passive"))
      (node (ref "R111") (pin "1") (pinfunction "1_1") (pintype "passive"))
      (node (ref "R113") (pin "1") (pinfunction "1_1") (pintype "passive"))
      (node (ref "R114") (pin "1") (pinfunction "1_1") (pintype "passive"))
      (node (ref "R115") (pin "1") (pinfunction "1_1") (pintype "passive"))
      (node (ref "R117") (pin "1") (pinfunction "1_1") (pintype "passive"))
      (node (ref "R118") (pin "1") (pinfunction "1_1") (pintype "passive"))
      (node (ref "R70") (pin "1") (pinfunction "1_1") (pintype "passive"))
      (node (ref "R71") (pin "1") (pinfunction "1_1") (pintype "passive"))
      (node (ref "R73") (pin "1") (pinfunction "1_1") (pintype "passive"))
      (node (ref "R74") (pin "1") (pinfunction "1_1") (pintype "passive"))
      (node (ref "R76") (pin "1") (pinfunction "1_1") (pintype "passive"))
      (node (ref "R77") (pin "1") (pinfunction "1_1") (pintype "passive"))
      (node (ref "R78") (pin "1") (pinfunction "1_1") (pintype "passive"))
      (node (ref "R80") (pin "1") (pinfunction "1_1") (pintype "passive"))
      (node (ref "U7") (pin "2") (pintype "passive"))
      (node (ref "U7") (pin "4") (pintype "passive"))
      (node (ref "U7") (pin "6") (pintype "passive"))
      (node (ref "U7") (pin "8") (pintype "passive"))
      (node (ref "VD4") (pin "2") (pinfunction "A_2") (pintype "passive"))
      (node (ref "VD5") (pin "2") (pinfunction "A_2") (pintype "passive"))
      (node (ref "VD6") (pin "2") (pinfunction "A_2") (pintype "passive"))
      (node (ref "VD7") (pin "2") (pinfunction "A_2") (pintype "passive"))
      (node (ref "XP9") (pin "16") (pintype "passive"))
      (node (ref "XP9") (pin "20") (pintype "passive"))
      (node (ref "XP9") (pin "7") (pintype "passive"))
    )
    (net (code "47") (name "Net-(DA19-IN+)") (class "Default")
      (node (ref "C101") (pin "1") (pinfunction "1_1") (pintype "passive"))
      (node (ref "DA19") (pin "3") (pinfunction "IN+_3") (pintype "passive"))
      (node (ref "R92") (pin "2") (pinfunction "2_2") (pintype "passive"))
      (node (ref "R96") (pin "1") (pinfunction "1_1") (pintype "passive"))
    )
    (net (code "48") (name "Net-(DA19-IN-)") (class "Default")
      (node (ref "C104") (pin "1") (pinfunction "1_1") (pintype "passive"))
      (node (ref "DA19") (pin "4") (pinfunction "IN-_4") (pintype "passive"))
      (node (ref "R95") (pin "2") (pinfunction "2_2") (pintype "passive"))
      (node (ref "R97") (pin "2") (pinfunction "2_2") (pintype "passive"))
    )
    (net (code "49") (name "Net-(DA22-IN+)") (class "Default")
      (node (ref "C111") (pin "1") (pinfunction "1_1") (pintype "passive"))
      (node (ref "DA22") (pin "3") (pinfunction "IN+_3") (pintype "passive"))
      (node (ref "R102") (pin "2") (pinfunction "2_2") (pintype "passive"))
    )
    (net (code "50") (name "Net-(DA22-IN-)") (class "Default")
      (node (ref "DA22") (pin "4") (pinfunction "IN-_4") (pintype "passive"))
      (node (ref "R112") (pin "2") (pinfunction "2_2") (pintype "passive"))
      (node (ref "R116") (pin "1") (pinfunction "1_1") (pintype "passive"))
    )
    (net (code "51") (name "Net-(DD11-VIA)") (class "Default")
      (node (ref "DD11") (pin "3") (pinfunction "VIA_3") (pintype "passive"))
      (node (ref "R88") (pin "2") (pinfunction "2_2") (pintype "passive"))
      (node (ref "VD7") (pin "1") (pinfunction "K_1") (pintype "passive"))
    )
    (net (code "52") (name "Net-(DD11-VIB)") (class "Default")
      (node (ref "DD11") (pin "4") (pinfunction "VIB_4") (pintype "passive"))
      (node (ref "R82") (pin "2") (pinfunction "2_2") (pintype "passive"))
      (node (ref "VD6") (pin "1") (pinfunction "K_1") (pintype "passive"))
    )
    (net (code "53") (name "Net-(DD11-VIC)") (class "Default")
      (node (ref "DD11") (pin "5") (pinfunction "VIC_5") (pintype "passive"))
      (node (ref "R89") (pin "2") (pinfunction "2_2") (pintype "passive"))
      (node (ref "VD5") (pin "1") (pinfunction "K_1") (pintype "passive"))
    )
    (net (code "54") (name "Net-(DD11-VID)") (class "Default")
      (node (ref "DD11") (pin "6") (pinfunction "VID_6") (pintype "passive"))
      (node (ref "R83") (pin "2") (pinfunction "2_2") (pintype "passive"))
      (node (ref "VD4") (pin "1") (pinfunction "K_1") (pintype "passive"))
    )
    (net (code "55") (name "Net-(DD12-VO)") (class "Default")
      (node (ref "DD12") (pin "6") (pinfunction "VO_6") (pintype "passive"))
      (node (ref "R102") (pin "1") (pinfunction "1_1") (pintype "passive"))
    )
    (net (code "56") (name "Net-(R84-Pad2)") (class "Default")
      (node (ref "R84") (pin "2") (pinfunction "2_2") (pintype "passive"))
      (node (ref "U7") (pin "1") (pintype "passive"))
    )
    (net (code "57") (name "Net-(R85-Pad2)") (class "Default")
      (node (ref "R85") (pin "2") (pinfunction "2_2") (pintype "passive"))
      (node (ref "U7") (pin "3") (pintype "passive"))
    )
    (net (code "58") (name "Net-(R86-Pad2)") (class "Default")
      (node (ref "R86") (pin "2") (pinfunction "2_2") (pintype "passive"))
      (node (ref "U7") (pin "5") (pintype "passive"))
    )
    (net (code "59") (name "Net-(R87-Pad2)") (class "Default")
      (node (ref "R87") (pin "2") (pinfunction "2_2") (pintype "passive"))
      (node (ref "U7") (pin "7") (pintype "passive"))
    )
    (net (code "60") (name "Net-(R98-Pad1)") (class "Default")
      (node (ref "R98") (pin "1") (pinfunction "1_1") (pintype "passive"))
      (node (ref "U8") (pin "1") (pintype "passive"))
    )
    (net (code "61") (name "Net-(R99-Pad1)") (class "Default")
      (node (ref "R99") (pin "1") (pinfunction "1_1") (pintype "passive"))
      (node (ref "U8") (pin "3") (pintype "passive"))
    )
    (net (code "62") (name "Net-(R100-Pad1)") (class "Default")
      (node (ref "R100") (pin "1") (pinfunction "1_1") (pintype "passive"))
      (node (ref "U8") (pin "5") (pintype "passive"))
    )
    (net (code "63") (name "Net-(R101-Pad1)") (class "Default")
      (node (ref "R101") (pin "1") (pinfunction "1_1") (pintype "passive"))
      (node (ref "U8") (pin "7") (pintype "passive"))
    )
    (net (code "64") (name "Net-(R103-Pad1)") (class "Default")
      (node (ref "R103") (pin "1") (pinfunction "1_1") (pintype "passive"))
      (node (ref "R107") (pin "1") (pinfunction "1_1") (pintype "passive"))
      (node (ref "U8") (pin "16") (pintype "passive"))
    )
    (net (code "65") (name "Net-(R104-Pad1)") (class "Default")
      (node (ref "R104") (pin "1") (pinfunction "1_1") (pintype "passive"))
      (node (ref "R108") (pin "1") (pinfunction "1_1") (pintype "passive"))
      (node (ref "U8") (pin "14") (pintype "passive"))
    )
    (net (code "66") (name "Net-(R105-Pad1)") (class "Default")
      (node (ref "R105") (pin "1") (pinfunction "1_1") (pintype "passive"))
      (node (ref "R109") (pin "1") (pinfunction "1_1") (pintype "passive"))
      (node (ref "U8") (pin "12") (pintype "passive"))
    )
    (net (code "67") (name "Net-(R106-Pad1)") (class "Default")
      (node (ref "R106") (pin "1") (pinfunction "1_1") (pintype "passive"))
      (node (ref "R110") (pin "1") (pinfunction "1_1") (pintype "passive"))
      (node (ref "U8") (pin "10") (pintype "passive"))
    )
    (net (code "68") (name "Net-(U6-VIN)") (class "Default")
      (node (ref "C96") (pin "2") (pinfunction "2_2") (pintype "passive"))
      (node (ref "R75") (pin "1") (pinfunction "1_1") (pintype "passive"))
      (node (ref "R79") (pin "1") (pinfunction "1_1") (pintype "passive"))
      (node (ref "U6") (pin "2") (pinfunction "VIN_2") (pintype "passive"))
    )
    (net (code "69") (name "Net-(U6-VOUT+)") (class "Default")
      (node (ref "R92") (pin "1") (pinfunction "1_1") (pintype "passive"))
      (node (ref "U6") (pin "7") (pinfunction "VOUT+_7") (pintype "passive"))
    )
    (net (code "70") (name "Net-(U6-VOUT-)") (class "Default")
      (node (ref "R95") (pin "1") (pinfunction "1_1") (pintype "passive"))
      (node (ref "U6") (pin "6") (pinfunction "VOUT-_6") (pintype "passive"))
    )
    (net (code "71") (name "unconnected-(DA20-NC-Pad5)") (class "Default")
      (node (ref "DA20") (pin "5") (pinfunction "NC_5") (pintype "passive"))
    )
    (net (code "72") (name "unconnected-(DA20-NC-Pad8)") (class "Default")
      (node (ref "DA20") (pin "8") (pinfunction "NC_8") (pintype "passive"))
    )
    (net (code "73") (name "unconnected-(DA20-ON{slash}OFF-Pad3)") (class "Default")
      (node (ref "DA20") (pin "3") (pinfunction "ON/OFF_3") (pintype "passive"))
    )
    (net (code "74") (name "unconnected-(DD10-NC-Pad10)") (class "Default")
      (node (ref "DD10") (pin "10") (pinfunction "NC_10") (pintype "passive"))
    )
    (net (code "75") (name "unconnected-(DD10-NC-Pad11)") (class "Default")
      (node (ref "DD10") (pin "11") (pinfunction "NC_11") (pintype "passive"))
    )
    (net (code "76") (name "unconnected-(DD10-NC-Pad14)") (class "Default")
      (node (ref "DD10") (pin "14") (pinfunction "NC_14") (pintype "passive"))
    )
    (net (code "77") (name "unconnected-(DD11-NC-Pad7)") (class "Default")
      (node (ref "DD11") (pin "7") (pinfunction "NC_7") (pintype "passive"))
    )
  )
)
